# standoff_board_v10.net
KiCad netlist of a schematic drawn in EAGLE
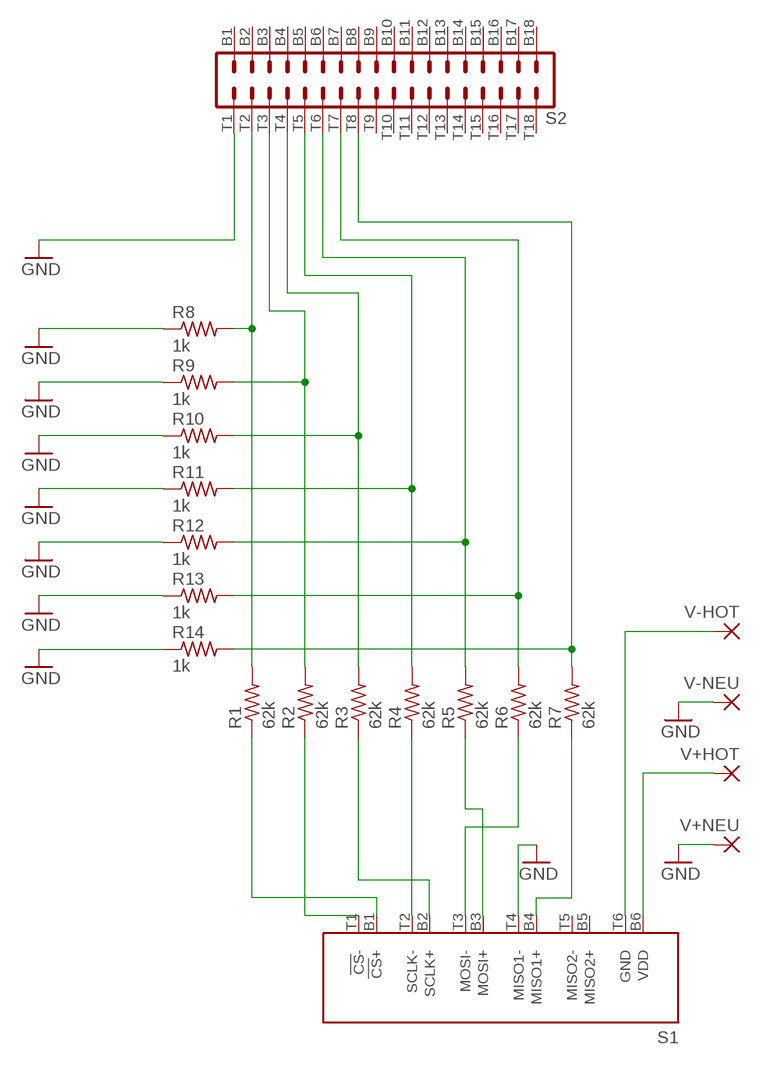
[diagram p0: schematic, sheet 1]

(export (version "E")
  (design (tool "Eeschema 10.0.6"))
  (components
    (comp (ref "R1")
      (value "62k")
      (footprint "eagle-import:0204_7")
      (libsource (lib "eagle-import") (part "R-US_0204/7"))
    )
    (comp (ref "R2")
      (value "62k")
      (footprint "eagle-import:0204_7")
      (libsource (lib "eagle-import") (part "R-US_0204/7"))
    )
    (comp (ref "R3")
      (value "62k")
      (footprint "eagle-import:0204_7")
      (libsource (lib "eagle-import") (part "R-US_0204/7"))
    )
    (comp (ref "R4")
      (value "62k")
      (footprint "eagle-import:0204_7")
      (libsource (lib "eagle-import") (part "R-US_0204/7"))
    )
    (comp (ref "R5")
      (value "62k")
      (footprint "eagle-import:0204_7")
      (libsource (lib "eagle-import") (part "R-US_0204/7"))
    )
    (comp (ref "R6")
      (value "62k")
      (footprint "eagle-import:0204_7")
      (libsource (lib "eagle-import") (part "R-US_0204/7"))
    )
    (comp (ref "R7")
      (value "62k")
      (footprint "eagle-import:0204_7")
      (libsource (lib "eagle-import") (part "R-US_0204/7"))
    )
    (comp (ref "R8")
      (value "1k")
      (footprint "eagle-import:0204_7")
      (libsource (lib "eagle-import") (part "R-US_0204/7"))
    )
    (comp (ref "R9")
      (value "1k")
      (footprint "eagle-import:0204_7")
      (libsource (lib "eagle-import") (part "R-US_0204/7"))
    )
    (comp (ref "R10")
      (value "1k")
      (footprint "eagle-import:0204_7")
      (libsource (lib "eagle-import") (part "R-US_0204/7"))
    )
    (comp (ref "R11")
      (value "1k")
      (footprint "eagle-import:0204_7")
      (libsource (lib "eagle-import") (part "R-US_0204/7"))
    )
    (comp (ref "R12")
      (value "1k")
      (footprint "eagle-import:0204_7")
      (libsource (lib "eagle-import") (part "R-US_0204/7"))
    )
    (comp (ref "R13")
      (value "1k")
      (footprint "eagle-import:0204_7")
      (libsource (lib "eagle-import") (part "R-US_0204/7"))
    )
    (comp (ref "R14")
      (value "1k")
      (footprint "eagle-import:0204_7")
      (libsource (lib "eagle-import") (part "R-US_0204/7"))
    )
    (comp (ref "S1")
      (value "RHD2000-CABLE-DAQ-SIDE")
      (footprint "eagle-import:OMNETICS_PZN-12-AA")
      (libsource (lib "eagle-import") (part "RHD2000-CABLE-DAQ-SIDE"))
    )
    (comp (ref "S2")
      (value "OMNETICS_A79025")
      (footprint "eagle-import:OMNETICS_A79025")
      (libsource (lib "eagle-import") (part "OMNETICS_A79025"))
    )
    (comp (ref "V+HOT")
      (value "2,54/1,1")
      (footprint "eagle-import:2,54_1,1")
      (libsource (lib "eagle-import") (part "2,54/1,1"))
    )
    (comp (ref "V+NEU")
      (value "2,54/1,1")
      (footprint "eagle-import:2,54_1,1")
      (libsource (lib "eagle-import") (part "2,54/1,1"))
    )
    (comp (ref "V-HOT")
      (value "2,54/1,1")
      (footprint "eagle-import:2,54_1,1")
      (libsource (lib "eagle-import") (part "2,54/1,1"))
    )
    (comp (ref "V-NEU")
      (value "2,54/1,1")
      (footprint "eagle-import:2,54_1,1")
      (libsource (lib "eagle-import") (part "2,54/1,1"))
    )
  )
  (nets
    (net (code "1") (name "GND") (class "Default")
      (node (ref "R10") (pin "1") (pinfunction "1_1") (pintype "passive"))
      (node (ref "R11") (pin "1") (pinfunction "1_1") (pintype "passive"))
      (node (ref "R12") (pin "1") (pinfunction "1_1") (pintype "passive"))
      (node (ref "R13") (pin "1") (pinfunction "1_1") (pintype "passive"))
      (node (ref "R14") (pin "1") (pinfunction "1_1") (pintype "passive"))
      (node (ref "R8") (pin "1") (pinfunction "1_1") (pintype "passive"))
      (node (ref "R9") (pin "1") (pinfunction "1_1") (pintype "passive"))
      (node (ref "S1") (pin "T4") (pinfunction "MISO1-_T4") (pintype "bidirectional"))
      (node (ref "S2") (pin "T1") (pinfunction "T1_T1") (pintype "passive"))
      (node (ref "V+NEU") (pin "1") (pinfunction "P_1") (pintype "passive"))
      (node (ref "V-NEU") (pin "1") (pinfunction "P_1") (pintype "passive"))
    )
    (net (code "2") (name "Net-(R1-Pad2)") (class "Default")
      (node (ref "R1") (pin "2") (pinfunction "2_2") (pintype "passive"))
      (node (ref "R8") (pin "2") (pinfunction "2_2") (pintype "passive"))
      (node (ref "S2") (pin "T2") (pinfunction "T2_T2") (pintype "passive"))
    )
    (net (code "3") (name "Net-(R2-Pad2)") (class "Default")
      (node (ref "R2") (pin "2") (pinfunction "2_2") (pintype "passive"))
      (node (ref "R9") (pin "2") (pinfunction "2_2") (pintype "passive"))
      (node (ref "S2") (pin "T3") (pinfunction "T3_T3") (pintype "passive"))
    )
    (net (code "4") (name "Net-(R10-Pad2)") (class "Default")
      (node (ref "R10") (pin "2") (pinfunction "2_2") (pintype "passive"))
      (node (ref "R3") (pin "2") (pinfunction "2_2") (pintype "passive"))
      (node (ref "S2") (pin "T4") (pinfunction "T4_T4") (pintype "passive"))
    )
    (net (code "5") (name "Net-(R11-Pad2)") (class "Default")
      (node (ref "R11") (pin "2") (pinfunction "2_2") (pintype "passive"))
      (node (ref "R4") (pin "2") (pinfunction "2_2") (pintype "passive"))
      (node (ref "S2") (pin "T5") (pinfunction "T5_T5") (pintype "passive"))
    )
    (net (code "6") (name "Net-(R12-Pad2)") (class "Default")
      (node (ref "R12") (pin "2") (pinfunction "2_2") (pintype "passive"))
      (node (ref "R5") (pin "2") (pinfunction "2_2") (pintype "passive"))
      (node (ref "S2") (pin "T6") (pinfunction "T6_T6") (pintype "passive"))
    )
    (net (code "7") (name "Net-(R13-Pad2)") (class "Default")
      (node (ref "R13") (pin "2") (pinfunction "2_2") (pintype "passive"))
      (node (ref "R6") (pin "2") (pinfunction "2_2") (pintype "passive"))
      (node (ref "S2") (pin "T7") (pinfunction "T7_T7") (pintype "passive"))
    )
    (net (code "8") (name "Net-(R14-Pad2)") (class "Default")
      (node (ref "R14") (pin "2") (pinfunction "2_2") (pintype "passive"))
      (node (ref "R7") (pin "2") (pinfunction "2_2") (pintype "passive"))
      (node (ref "S2") (pin "T8") (pinfunction "T8_T8") (pintype "passive"))
    )
    (net (code "9") (name "Net-(S1-GND)") (class "Default")
      (node (ref "S1") (pin "T6") (pinfunction "GND_T6") (pintype "power_in"))
      (node (ref "V-HOT") (pin "1") (pinfunction "P_1") (pintype "passive"))
    )
    (net (code "10") (name "Net-(S1-MISO1+)") (class "Default")
      (node (ref "R7") (pin "1") (pinfunction "1_1") (pintype "passive"))
      (node (ref "S1") (pin "B4") (pinfunction "MISO1+_B4") (pintype "bidirectional"))
    )
    (net (code "11") (name "Net-(S1-MOSI+)") (class "Default")
      (node (ref "R5") (pin "1") (pinfunction "1_1") (pintype "passive"))
      (node (ref "S1") (pin "B3") (pinfunction "MOSI+_B3") (pintype "bidirectional"))
    )
    (net (code "12") (name "Net-(S1-MOSI-)") (class "Default")
      (node (ref "R6") (pin "1") (pinfunction "1_1") (pintype "passive"))
      (node (ref "S1") (pin "T3") (pinfunction "MOSI-_T3") (pintype "bidirectional"))
    )
    (net (code "13") (name "Net-(S1-SCLK+)") (class "Default")
      (node (ref "R3") (pin "1") (pinfunction "1_1") (pintype "passive"))
      (node (ref "S1") (pin "B2") (pinfunction "SCLK+_B2") (pintype "bidirectional"))
    )
    (net (code "14") (name "Net-(S1-SCLK-)") (class "Default")
      (node (ref "R4") (pin "1") (pinfunction "1_1") (pintype "passive"))
      (node (ref "S1") (pin "T2") (pinfunction "SCLK-_T2") (pintype "bidirectional"))
    )
    (net (code "15") (name "Net-(S1-VDD)") (class "Default")
      (node (ref "S1") (pin "B6") (pinfunction "VDD_B6") (pintype "bidirectional"))
      (node (ref "V+HOT") (pin "1") (pinfunction "P_1") (pintype "passive"))
    )
    (net (code "16") (name "Net-(S1-~{CS}+)") (class "Default")
      (node (ref "R1") (pin "1") (pinfunction "1_1") (pintype "passive"))
      (node (ref "S1") (pin "B1") (pinfunction "~{CS}+_B1") (pintype "bidirectional"))
    )
    (net (code "17") (name "Net-(S1-~{CS}-)") (class "Default")
      (node (ref "R2") (pin "1") (pinfunction "1_1") (pintype "passive"))
      (node (ref "S1") (pin "T1") (pinfunction "~{CS}-_T1") (pintype "bidirectional"))
    )
    (net (code "18") (name "unconnected-(S1-MISO2+-PadB5)") (class "Default")
      (node (ref "S1") (pin "B5") (pinfunction "MISO2+_B5") (pintype "bidirectional"))
    )
    (net (code "19") (name "unconnected-(S1-MISO2--PadT5)") (class "Default")
      (node (ref "S1") (pin "T5") (pinfunction "MISO2-_T5") (pintype "bidirectional"))
    )
    (net (code "20") (name "unconnected-(S2-PadB1)") (class "Default")
      (node (ref "S2") (pin "B1") (pinfunction "B1_B1") (pintype "passive"))
    )
    (net (code "21") (name "unconnected-(S2-PadB2)") (class "Default")
      (node (ref "S2") (pin "B2") (pinfunction "B2_B2") (pintype "passive"))
    )
    (net (code "22") (name "unconnected-(S2-PadB3)") (class "Default")
      (node (ref "S2") (pin "B3") (pinfunction "B3_B3") (pintype "passive"))
    )
    (net (code "23") (name "unconnected-(S2-PadB4)") (class "Default")
      (node (ref "S2") (pin "B4") (pinfunction "B4_B4") (pintype "passive"))
    )
    (net (code "24") (name "unconnected-(S2-PadB5)") (class "Default")
      (node (ref "S2") (pin "B5") (pinfunction "B5_B5") (pintype "passive"))
    )
    (net (code "25") (name "unconnected-(S2-PadB6)") (class "Default")
      (node (ref "S2") (pin "B6") (pinfunction "B6_B6") (pintype "passive"))
    )
    (net (code "26") (name "unconnected-(S2-PadB7)") (class "Default")
      (node (ref "S2") (pin "B7") (pinfunction "B7_B7") (pintype "passive"))
    )
    (net (code "27") (name "unconnected-(S2-PadB8)") (class "Default")
      (node (ref "S2") (pin "B8") (pinfunction "B8_B8") (pintype "passive"))
    )
    (net (code "28") (name "unconnected-(S2-PadB9)") (class "Default")
      (node (ref "S2") (pin "B9") (pinfunction "B9_B9") (pintype "passive"))
    )
    (net (code "29") (name "unconnected-(S2-PadB10)") (class "Default")
      (node (ref "S2") (pin "B10") (pinfunction "B10_B10") (pintype "passive"))
    )
    (net (code "30") (name "unconnected-(S2-PadB11)") (class "Default")
      (node (ref "S2") (pin "B11") (pinfunction "B11_B11") (pintype "passive"))
    )
    (net (code "31") (name "unconnected-(S2-PadB12)") (class "Default")
      (node (ref "S2") (pin "B12") (pinfunction "B12_B12") (pintype "passive"))
    )
    (net (code "32") (name "unconnected-(S2-PadB13)") (class "Default")
      (node (ref "S2") (pin "B13") (pinfunction "B13_B13") (pintype "passive"))
    )
    (net (code "33") (name "unconnected-(S2-PadB14)") (class "Default")
      (node (ref "S2") (pin "B14") (pinfunction "B14_B14") (pintype "passive"))
    )
    (net (code "34") (name "unconnected-(S2-PadB15)") (class "Default")
      (node (ref "S2") (pin "B15") (pinfunction "B15_B15") (pintype "passive"))
    )
    (net (code "35") (name "unconnected-(S2-PadB16)") (class "Default")
      (node (ref "S2") (pin "B16") (pinfunction "B16_B16") (pintype "passive"))
    )
    (net (code "36") (name "unconnected-(S2-PadB17)") (class "Default")
      (node (ref "S2") (pin "B17") (pinfunction "B17_B17") (pintype "passive"))
    )
    (net (code "37") (name "unconnected-(S2-PadB18)") (class "Default")
      (node (ref "S2") (pin "B18") (pinfunction "B18_B18") (pintype "passive"))
    )
    (net (code "38") (name "unconnected-(S2-PadT9)") (class "Default")
      (node (ref "S2") (pin "T9") (pinfunction "T9_T9") (pintype "passive"))
    )
    (net (code "39") (name "unconnected-(S2-PadT10)") (class "Default")
      (node (ref "S2") (pin "T10") (pinfunction "T10_T10") (pintype "passive"))
    )
    (net (code "40") (name "unconnected-(S2-PadT11)") (class "Default")
      (node (ref "S2") (pin "T11") (pinfunction "T11_T11") (pintype "passive"))
    )
    (net (code "41") (name "unconnected-(S2-PadT12)") (class "Default")
      (node (ref "S2") (pin "T12") (pinfunction "T12_T12") (pintype "passive"))
    )
    (net (code "42") (name "unconnected-(S2-PadT13)") (class "Default")
      (node (ref "S2") (pin "T13") (pinfunction "T13_T13") (pintype "passive"))
    )
    (net (code "43") (name "unconnected-(S2-PadT14)") (class "Default")
      (node (ref "S2") (pin "T14") (pinfunction "T14_T14") (pintype "passive"))
    )
    (net (code "44") (name "unconnected-(S2-PadT15)") (class "Default")
      (node (ref "S2") (pin "T15") (pinfunction "T15_T15") (pintype "passive"))
    )
    (net (code "45") (name "unconnected-(S2-PadT16)") (class "Default")
      (node (ref "S2") (pin "T16") (pinfunction "T16_T16") (pintype "passive"))
    )
    (net (code "46") (name "unconnected-(S2-PadT17)") (class "Default")
      (node (ref "S2") (pin "T17") (pinfunction "T17_T17") (pintype "passive"))
    )
    (net (code "47") (name "unconnected-(S2-PadT18)") (class "Default")
      (node (ref "S2") (pin "T18") (pinfunction "T18_T18") (pintype "passive"))
    )
  )
)
